# Sheet1.net
KiCad netlist of a schematic drawn in Altium Designer
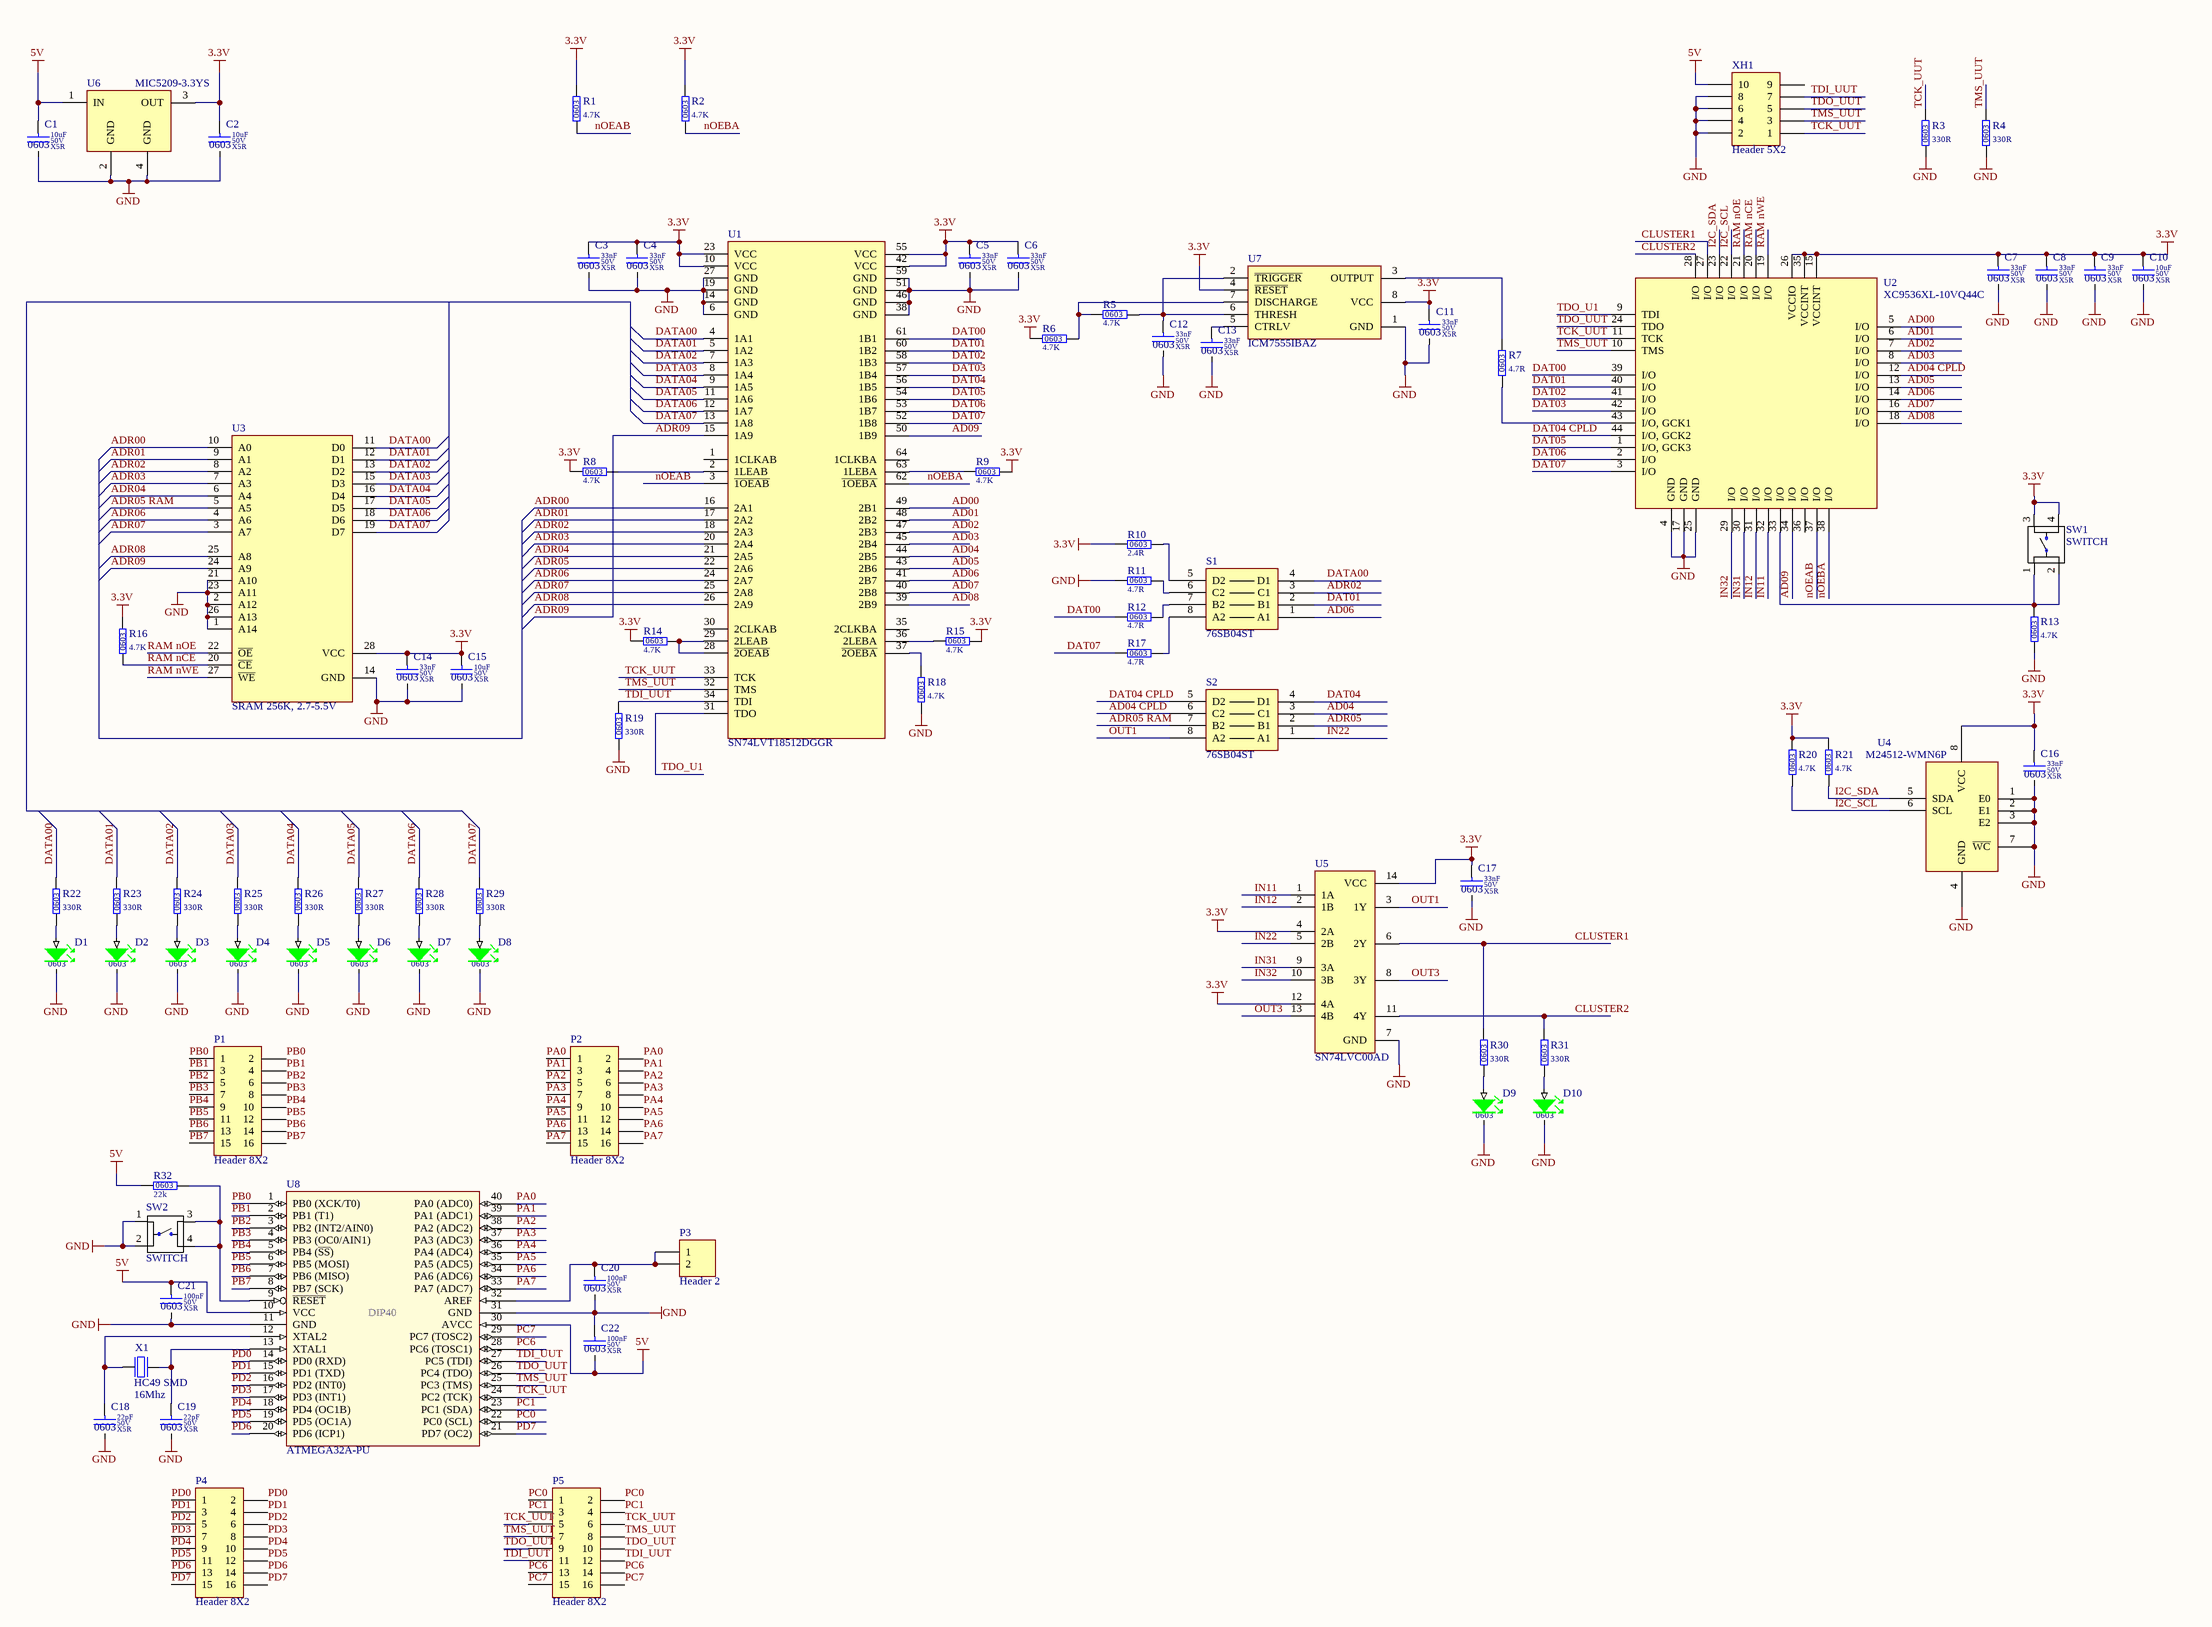
[diagram p0: Sheet1.SchDoc]

(export (version "E")
  (design (tool "Eeschema 10.0.6"))
  (components
    (comp (ref "C1")
      (value "10uF")
      (footprint "C_0603")
      (description "Capacitor")
      (fields
        (field (name "DIELECTRIC") "X5R")
        (field (name "VOLTAGE") "50V")
        (field (name "SCH_FOOTPRINT") "0603")
        (field (name "PART NUMBER") "C_10uF_50V_X5R_0603_10")
        (field (name "TOLERANCE") "10%")
      )
      (libsource (lib "MatyczLib") (part "C"))
    )
    (comp (ref "C2")
      (value "10uF")
      (footprint "C_0603")
      (description "Capacitor")
      (fields
        (field (name "DIELECTRIC") "X5R")
        (field (name "VOLTAGE") "50V")
        (field (name "SCH_FOOTPRINT") "0603")
        (field (name "PART NUMBER") "C_10uF_50V_X5R_0603_10")
        (field (name "TOLERANCE") "10%")
      )
      (libsource (lib "MatyczLib") (part "C"))
    )
    (comp (ref "C3")
      (value "33nF")
      (footprint "C_0603")
      (description "Capacitor")
      (fields
        (field (name "DIELECTRIC") "X5R")
        (field (name "VOLTAGE") "50V")
        (field (name "SCH_FOOTPRINT") "0603")
        (field (name "PART NUMBER") "C_33nF_50V_X5R_0603_10")
        (field (name "TOLERANCE") "10%")
      )
      (libsource (lib "MatyczLib") (part "C"))
    )
    (comp (ref "C4")
      (value "33nF")
      (footprint "C_0603")
      (description "Capacitor")
      (fields
        (field (name "DIELECTRIC") "X5R")
        (field (name "VOLTAGE") "50V")
        (field (name "SCH_FOOTPRINT") "0603")
        (field (name "PART NUMBER") "C_33nF_50V_X5R_0603_10")
        (field (name "TOLERANCE") "10%")
      )
      (libsource (lib "MatyczLib") (part "C"))
    )
    (comp (ref "C5")
      (value "33nF")
      (footprint "C_0603")
      (description "Capacitor")
      (fields
        (field (name "DIELECTRIC") "X5R")
        (field (name "VOLTAGE") "50V")
        (field (name "SCH_FOOTPRINT") "0603")
        (field (name "PART NUMBER") "C_33nF_50V_X5R_0603_10")
        (field (name "TOLERANCE") "10%")
      )
      (libsource (lib "MatyczLib") (part "C"))
    )
    (comp (ref "C6")
      (value "33nF")
      (footprint "C_0603")
      (description "Capacitor")
      (fields
        (field (name "DIELECTRIC") "X5R")
        (field (name "VOLTAGE") "50V")
        (field (name "SCH_FOOTPRINT") "0603")
        (field (name "PART NUMBER") "C_33nF_50V_X5R_0603_10")
        (field (name "TOLERANCE") "10%")
      )
      (libsource (lib "MatyczLib") (part "C"))
    )
    (comp (ref "C7")
      (value "33nF")
      (footprint "C_0603")
      (description "Capacitor")
      (fields
        (field (name "DIELECTRIC") "X5R")
        (field (name "VOLTAGE") "50V")
        (field (name "SCH_FOOTPRINT") "0603")
        (field (name "PART NUMBER") "C_33nF_50V_X5R_0603_10")
        (field (name "TOLERANCE") "10%")
      )
      (libsource (lib "MatyczLib") (part "C"))
    )
    (comp (ref "C8")
      (value "33nF")
      (footprint "C_0603")
      (description "Capacitor")
      (fields
        (field (name "DIELECTRIC") "X5R")
        (field (name "VOLTAGE") "50V")
        (field (name "SCH_FOOTPRINT") "0603")
        (field (name "PART NUMBER") "C_33nF_50V_X5R_0603_10")
        (field (name "TOLERANCE") "10%")
      )
      (libsource (lib "MatyczLib") (part "C"))
    )
    (comp (ref "C9")
      (value "33nF")
      (footprint "C_0603")
      (description "Capacitor")
      (fields
        (field (name "DIELECTRIC") "X5R")
        (field (name "VOLTAGE") "50V")
        (field (name "SCH_FOOTPRINT") "0603")
        (field (name "PART NUMBER") "C_33nF_50V_X5R_0603_10")
        (field (name "TOLERANCE") "10%")
      )
      (libsource (lib "MatyczLib") (part "C"))
    )
    (comp (ref "C10")
      (value "10uF")
      (footprint "C_0603")
      (description "Capacitor")
      (fields
        (field (name "DIELECTRIC") "X5R")
        (field (name "VOLTAGE") "50V")
        (field (name "SCH_FOOTPRINT") "0603")
        (field (name "PART NUMBER") "C_10uF_50V_X5R_0603_10")
        (field (name "TOLERANCE") "10%")
      )
      (libsource (lib "MatyczLib") (part "C"))
    )
    (comp (ref "C11")
      (value "33nF")
      (footprint "C_0603")
      (description "Capacitor")
      (fields
        (field (name "DIELECTRIC") "X5R")
        (field (name "VOLTAGE") "50V")
        (field (name "SCH_FOOTPRINT") "0603")
        (field (name "PART NUMBER") "C_33nF_50V_X5R_0603_10")
        (field (name "TOLERANCE") "10%")
      )
      (libsource (lib "MatyczLib") (part "C"))
    )
    (comp (ref "C12")
      (value "33nF")
      (footprint "C_0603")
      (description "Capacitor")
      (fields
        (field (name "DIELECTRIC") "X5R")
        (field (name "VOLTAGE") "50V")
        (field (name "SCH_FOOTPRINT") "0603")
        (field (name "PART NUMBER") "C_33nF_50V_X5R_0603_10")
        (field (name "TOLERANCE") "10%")
      )
      (libsource (lib "MatyczLib") (part "C"))
    )
    (comp (ref "C13")
      (value "33nF")
      (footprint "C_0603")
      (description "Capacitor")
      (fields
        (field (name "DIELECTRIC") "X5R")
        (field (name "VOLTAGE") "50V")
        (field (name "SCH_FOOTPRINT") "0603")
        (field (name "PART NUMBER") "C_33nF_50V_X5R_0603_10")
        (field (name "TOLERANCE") "10%")
      )
      (libsource (lib "MatyczLib") (part "C"))
    )
    (comp (ref "C14")
      (value "33nF")
      (footprint "C_0603")
      (description "Capacitor")
      (fields
        (field (name "DIELECTRIC") "X5R")
        (field (name "VOLTAGE") "50V")
        (field (name "SCH_FOOTPRINT") "0603")
        (field (name "PART NUMBER") "C_33nF_50V_X5R_0603_10")
        (field (name "TOLERANCE") "10%")
      )
      (libsource (lib "MatyczLib") (part "C"))
    )
    (comp (ref "C15")
      (value "10uF")
      (footprint "C_0603")
      (description "Capacitor")
      (fields
        (field (name "DIELECTRIC") "X5R")
        (field (name "VOLTAGE") "50V")
        (field (name "SCH_FOOTPRINT") "0603")
        (field (name "PART NUMBER") "C_10uF_50V_X5R_0603_10")
        (field (name "TOLERANCE") "10%")
      )
      (libsource (lib "MatyczLib") (part "C"))
    )
    (comp (ref "C16")
      (value "33nF")
      (footprint "C_0603")
      (description "Capacitor")
      (fields
        (field (name "DIELECTRIC") "X5R")
        (field (name "VOLTAGE") "50V")
        (field (name "SCH_FOOTPRINT") "0603")
        (field (name "PART NUMBER") "C_33nF_50V_X5R_0603_10")
        (field (name "TOLERANCE") "10%")
      )
      (libsource (lib "MatyczLib") (part "C"))
    )
    (comp (ref "C17")
      (value "33nF")
      (footprint "C_0603")
      (description "Capacitor")
      (fields
        (field (name "DIELECTRIC") "X5R")
        (field (name "VOLTAGE") "50V")
        (field (name "SCH_FOOTPRINT") "0603")
        (field (name "PART NUMBER") "C_33nF_50V_X5R_0603_10")
        (field (name "TOLERANCE") "10%")
      )
      (libsource (lib "MatyczLib") (part "C"))
    )
    (comp (ref "C18")
      (value "22pF")
      (footprint "C_0603")
      (description "Capacitor")
      (fields
        (field (name "DIELECTRIC") "X5R")
        (field (name "VOLTAGE") "50V")
        (field (name "SCH_FOOTPRINT") "0603")
        (field (name "PART NUMBER") "C_22pF_50V_X5R_0603_10")
        (field (name "TOLERANCE") "10%")
      )
      (libsource (lib "MatyczLib") (part "C"))
    )
    (comp (ref "C19")
      (value "22pF")
      (footprint "C_0603")
      (description "Capacitor")
      (fields
        (field (name "DIELECTRIC") "X5R")
        (field (name "VOLTAGE") "50V")
        (field (name "SCH_FOOTPRINT") "0603")
        (field (name "PART NUMBER") "C_22pF_50V_X5R_0603_10")
        (field (name "TOLERANCE") "10%")
      )
      (libsource (lib "MatyczLib") (part "C"))
    )
    (comp (ref "C20")
      (value "100nF")
      (footprint "C_0603")
      (description "Capacitor")
      (fields
        (field (name "DIELECTRIC") "X5R")
        (field (name "VOLTAGE") "50V")
        (field (name "SCH_FOOTPRINT") "0603")
        (field (name "PART NUMBER") "C_100nF_50V_X5R_0603_10")
        (field (name "TOLERANCE") "10%")
      )
      (libsource (lib "MatyczLib") (part "C"))
    )
    (comp (ref "C21")
      (value "100nF")
      (footprint "C_0603")
      (description "Capacitor")
      (fields
        (field (name "DIELECTRIC") "X5R")
        (field (name "VOLTAGE") "50V")
        (field (name "SCH_FOOTPRINT") "0603")
        (field (name "PART NUMBER") "C_100nF_50V_X5R_0603_10")
        (field (name "TOLERANCE") "10%")
      )
      (libsource (lib "MatyczLib") (part "C"))
    )
    (comp (ref "C22")
      (value "100nF")
      (footprint "C_0603")
      (description "Capacitor")
      (fields
        (field (name "DIELECTRIC") "X5R")
        (field (name "VOLTAGE") "50V")
        (field (name "SCH_FOOTPRINT") "0603")
        (field (name "PART NUMBER") "C_100nF_50V_X5R_0603_10")
        (field (name "TOLERANCE") "10%")
      )
      (libsource (lib "MatyczLib") (part "C"))
    )
    (comp (ref "D1")
      (value "Green Led")
      (footprint "OL_0603_1608")
      (description "LED GREEN")
      (fields
        (field (name "SCH_FOOTPRINT") "0603")
        (field (name "PART NUMBER") "OL_G_0603")
        (field (name "MANUFACTURER") "Lite-On")
      )
      (libsource (lib "Library") (part "OL_G"))
    )
    (comp (ref "D2")
      (value "Green Led")
      (footprint "OL_0603_1608")
      (description "LED GREEN")
      (fields
        (field (name "SCH_FOOTPRINT") "0603")
        (field (name "PART NUMBER") "OL_G_0603")
        (field (name "MANUFACTURER") "Lite-On")
      )
      (libsource (lib "Library") (part "OL_G"))
    )
    (comp (ref "D3")
      (value "Green Led")
      (footprint "OL_0603_1608")
      (description "LED GREEN")
      (fields
        (field (name "SCH_FOOTPRINT") "0603")
        (field (name "PART NUMBER") "OL_G_0603")
        (field (name "MANUFACTURER") "Lite-On")
      )
      (libsource (lib "Library") (part "OL_G"))
    )
    (comp (ref "D4")
      (value "Green Led")
      (footprint "OL_0603_1608")
      (description "LED GREEN")
      (fields
        (field (name "SCH_FOOTPRINT") "0603")
        (field (name "PART NUMBER") "OL_G_0603")
        (field (name "MANUFACTURER") "Lite-On")
      )
      (libsource (lib "Library") (part "OL_G"))
    )
    (comp (ref "D5")
      (value "Green Led")
      (footprint "OL_0603_1608")
      (description "LED GREEN")
      (fields
        (field (name "SCH_FOOTPRINT") "0603")
        (field (name "PART NUMBER") "OL_G_0603")
        (field (name "MANUFACTURER") "Lite-On")
      )
      (libsource (lib "Library") (part "OL_G"))
    )
    (comp (ref "D6")
      (value "Green Led")
      (footprint "OL_0603_1608")
      (description "LED GREEN")
      (fields
        (field (name "SCH_FOOTPRINT") "0603")
        (field (name "PART NUMBER") "OL_G_0603")
        (field (name "MANUFACTURER") "Lite-On")
      )
      (libsource (lib "Library") (part "OL_G"))
    )
    (comp (ref "D7")
      (value "Green Led")
      (footprint "OL_0603_1608")
      (description "LED GREEN")
      (fields
        (field (name "SCH_FOOTPRINT") "0603")
        (field (name "PART NUMBER") "OL_G_0603")
        (field (name "MANUFACTURER") "Lite-On")
      )
      (libsource (lib "Library") (part "OL_G"))
    )
    (comp (ref "D8")
      (value "Green Led")
      (footprint "OL_0603_1608")
      (description "LED GREEN")
      (fields
        (field (name "SCH_FOOTPRINT") "0603")
        (field (name "PART NUMBER") "OL_G_0603")
        (field (name "MANUFACTURER") "Lite-On")
      )
      (libsource (lib "Library") (part "OL_G"))
    )
    (comp (ref "D9")
      (value "Green Led")
      (footprint "OL_0603_1608")
      (description "LED GREEN")
      (fields
        (field (name "SCH_FOOTPRINT") "0603")
        (field (name "PART NUMBER") "OL_G_0603")
        (field (name "MANUFACTURER") "Lite-On")
      )
      (libsource (lib "Library") (part "OL_G"))
    )
    (comp (ref "D10")
      (value "Green Led")
      (footprint "OL_0603_1608")
      (description "LED GREEN")
      (fields
        (field (name "SCH_FOOTPRINT") "0603")
        (field (name "PART NUMBER") "OL_G_0603")
        (field (name "MANUFACTURER") "Lite-On")
      )
      (libsource (lib "Library") (part "OL_G"))
    )
    (comp (ref "P1")
      (value "Header 8X2")
      (footprint "HDR2X8")
      (description "Header, 8-Pin, Dual row")
      (fields (field (name "PUBLISHER") "Altium Limited"))
      (libsource (lib "Miscellaneous Connectors") (part "Header 8X2"))
    )
    (comp (ref "P2")
      (value "Header 8X2")
      (footprint "HDR2X8")
      (description "Header, 8-Pin, Dual row")
      (fields (field (name "PUBLISHER") "Altium Limited"))
      (libsource (lib "Miscellaneous Connectors") (part "Header 8X2"))
    )
    (comp (ref "P3")
      (value "Header 2")
      (footprint "HDR1X2")
      (description "Header, 2-Pin")
      (fields (field (name "PUBLISHER") "Altium Limited"))
      (libsource (lib "Miscellaneous Connectors") (part "Header 2"))
    )
    (comp (ref "P4")
      (value "Header 8X2")
      (footprint "HDR2X8")
      (description "Header, 8-Pin, Dual row")
      (fields (field (name "PUBLISHER") "Altium Limited"))
      (libsource (lib "Miscellaneous Connectors") (part "Header 8X2"))
    )
    (comp (ref "P5")
      (value "Header 8X2")
      (footprint "HDR2X8")
      (description "Header, 8-Pin, Dual row")
      (fields (field (name "PUBLISHER") "Altium Limited"))
      (libsource (lib "Miscellaneous Connectors") (part "Header 8X2"))
    )
    (comp (ref "R1")
      (value "4.7K")
      (footprint "R_0603")
      (fields
        (field (name "SCH_FOOTPRINT") "0603")
        (field (name "PART NUMBER") "R_4.7k_0603_5")
        (field (name "TOLERANCE") "5%")
        (field (name "POWER") "100mW")
      )
      (libsource (lib "") (part "R_1"))
    )
    (comp (ref "R2")
      (value "4.7K")
      (footprint "R_0603")
      (fields
        (field (name "SCH_FOOTPRINT") "0603")
        (field (name "PART NUMBER") "R_4.7k_0603_5")
        (field (name "TOLERANCE") "5%")
        (field (name "POWER") "100mW")
      )
      (libsource (lib "") (part "R_1"))
    )
    (comp (ref "R3")
      (value "330R")
      (footprint "R_0603")
      (fields
        (field (name "SCH_FOOTPRINT") "0603")
        (field (name "PART NUMBER") "R_330R_0603_5")
        (field (name "TOLERANCE") "5%")
        (field (name "POWER") "100mW")
      )
      (libsource (lib "") (part "R_1"))
    )
    (comp (ref "R4")
      (value "330R")
      (footprint "R_0603")
      (fields
        (field (name "SCH_FOOTPRINT") "0603")
        (field (name "PART NUMBER") "R_330R_0603_5")
        (field (name "TOLERANCE") "5%")
        (field (name "POWER") "100mW")
      )
      (libsource (lib "") (part "R_1"))
    )
    (comp (ref "R5")
      (value "4.7K")
      (footprint "R_0603")
      (fields
        (field (name "SCH_FOOTPRINT") "0603")
        (field (name "PART NUMBER") "R_4.7k_0603_5")
        (field (name "TOLERANCE") "5%")
        (field (name "POWER") "100mW")
      )
      (libsource (lib "MatyczLib") (part "R"))
    )
    (comp (ref "R6")
      (value "4.7K")
      (footprint "R_0603")
      (fields
        (field (name "SCH_FOOTPRINT") "0603")
        (field (name "PART NUMBER") "R_4.7k_0603_5")
        (field (name "TOLERANCE") "5%")
        (field (name "POWER") "100mW")
      )
      (libsource (lib "MatyczLib") (part "R"))
    )
    (comp (ref "R7")
      (value "4.7R")
      (footprint "R_0603")
      (fields
        (field (name "SCH_FOOTPRINT") "0603")
        (field (name "PART NUMBER") "R_4.7R_0603_5")
        (field (name "TOLERANCE") "5%")
        (field (name "POWER") "100mW")
      )
      (libsource (lib "") (part "R_1"))
    )
    (comp (ref "R8")
      (value "4.7K")
      (footprint "R_0603")
      (fields
        (field (name "SCH_FOOTPRINT") "0603")
        (field (name "PART NUMBER") "R_4.7k_0603_5")
        (field (name "TOLERANCE") "5%")
        (field (name "POWER") "100mW")
      )
      (libsource (lib "MatyczLib") (part "R"))
    )
    (comp (ref "R9")
      (value "4.7K")
      (footprint "R_0603")
      (fields
        (field (name "SCH_FOOTPRINT") "0603")
        (field (name "PART NUMBER") "R_4.7k_0603_5")
        (field (name "TOLERANCE") "5%")
        (field (name "POWER") "100mW")
      )
      (libsource (lib "MatyczLib") (part "R"))
    )
    (comp (ref "R10")
      (value "2.4R")
      (footprint "R_0603")
      (fields
        (field (name "SCH_FOOTPRINT") "0603")
        (field (name "PART NUMBER") "R_2.4R_0603_5")
        (field (name "TOLERANCE") "5%")
        (field (name "POWER") "100mW")
      )
      (libsource (lib "MatyczLib") (part "R"))
    )
    (comp (ref "R11")
      (value "4.7R")
      (footprint "R_0603")
      (fields
        (field (name "SCH_FOOTPRINT") "0603")
        (field (name "PART NUMBER") "R_4.7R_0603_5")
        (field (name "TOLERANCE") "5%")
        (field (name "POWER") "100mW")
      )
      (libsource (lib "MatyczLib") (part "R"))
    )
    (comp (ref "R12")
      (value "4.7R")
      (footprint "R_0603")
      (fields
        (field (name "SCH_FOOTPRINT") "0603")
        (field (name "PART NUMBER") "R_4.7R_0603_5")
        (field (name "TOLERANCE") "5%")
        (field (name "POWER") "100mW")
      )
      (libsource (lib "MatyczLib") (part "R"))
    )
    (comp (ref "R13")
      (value "4.7K")
      (footprint "R_0603")
      (fields
        (field (name "SCH_FOOTPRINT") "0603")
        (field (name "PART NUMBER") "R_4.7k_0603_5")
        (field (name "TOLERANCE") "5%")
        (field (name "POWER") "100mW")
      )
      (libsource (lib "") (part "R_1"))
    )
    (comp (ref "R14")
      (value "4.7K")
      (footprint "R_0603")
      (fields
        (field (name "SCH_FOOTPRINT") "0603")
        (field (name "PART NUMBER") "R_4.7k_0603_5")
        (field (name "TOLERANCE") "5%")
        (field (name "POWER") "100mW")
      )
      (libsource (lib "MatyczLib") (part "R"))
    )
    (comp (ref "R15")
      (value "4.7K")
      (footprint "R_0603")
      (fields
        (field (name "SCH_FOOTPRINT") "0603")
        (field (name "PART NUMBER") "R_4.7k_0603_5")
        (field (name "TOLERANCE") "5%")
        (field (name "POWER") "100mW")
      )
      (libsource (lib "MatyczLib") (part "R"))
    )
    (comp (ref "R16")
      (value "4.7K")
      (footprint "R_0603")
      (fields
        (field (name "SCH_FOOTPRINT") "0603")
        (field (name "PART NUMBER") "R_4.7k_0603_5")
        (field (name "TOLERANCE") "5%")
        (field (name "POWER") "100mW")
      )
      (libsource (lib "") (part "R_1"))
    )
    (comp (ref "R17")
      (value "4.7R")
      (footprint "R_0603")
      (fields
        (field (name "SCH_FOOTPRINT") "0603")
        (field (name "PART NUMBER") "R_4.7R_0603_5")
        (field (name "TOLERANCE") "5%")
        (field (name "POWER") "100mW")
      )
      (libsource (lib "MatyczLib") (part "R"))
    )
    (comp (ref "R18")
      (value "4.7K")
      (footprint "R_0603")
      (fields
        (field (name "SCH_FOOTPRINT") "0603")
        (field (name "PART NUMBER") "R_4.7k_0603_5")
        (field (name "TOLERANCE") "5%")
        (field (name "POWER") "100mW")
      )
      (libsource (lib "") (part "R_1"))
    )
    (comp (ref "R19")
      (value "330R")
      (footprint "R_0603")
      (fields
        (field (name "SCH_FOOTPRINT") "0603")
        (field (name "PART NUMBER") "R_330R_0603_5")
        (field (name "TOLERANCE") "5%")
        (field (name "POWER") "100mW")
      )
      (libsource (lib "") (part "R_1"))
    )
    (comp (ref "R20")
      (value "4.7K")
      (footprint "R_0603")
      (fields
        (field (name "SCH_FOOTPRINT") "0603")
        (field (name "PART NUMBER") "R_4.7k_0603_5")
        (field (name "TOLERANCE") "5%")
        (field (name "POWER") "100mW")
      )
      (libsource (lib "") (part "R_1"))
    )
    (comp (ref "R21")
      (value "4.7K")
      (footprint "R_0603")
      (fields
        (field (name "SCH_FOOTPRINT") "0603")
        (field (name "PART NUMBER") "R_4.7k_0603_5")
        (field (name "TOLERANCE") "5%")
        (field (name "POWER") "100mW")
      )
      (libsource (lib "") (part "R_1"))
    )
    (comp (ref "R22")
      (value "330R")
      (footprint "R_0603")
      (fields
        (field (name "SCH_FOOTPRINT") "0603")
        (field (name "PART NUMBER") "R_330R_0603_5")
        (field (name "TOLERANCE") "5%")
        (field (name "POWER") "100mW")
      )
      (libsource (lib "") (part "R_1"))
    )
    (comp (ref "R23")
      (value "330R")
      (footprint "R_0603")
      (fields
        (field (name "SCH_FOOTPRINT") "0603")
        (field (name "PART NUMBER") "R_330R_0603_5")
        (field (name "TOLERANCE") "5%")
        (field (name "POWER") "100mW")
      )
      (libsource (lib "") (part "R_1"))
    )
    (comp (ref "R24")
      (value "330R")
      (footprint "R_0603")
      (fields
        (field (name "SCH_FOOTPRINT") "0603")
        (field (name "PART NUMBER") "R_330R_0603_5")
        (field (name "TOLERANCE") "5%")
        (field (name "POWER") "100mW")
      )
      (libsource (lib "") (part "R_1"))
    )
    (comp (ref "R25")
      (value "330R")
      (footprint "R_0603")
      (fields
        (field (name "SCH_FOOTPRINT") "0603")
        (field (name "PART NUMBER") "R_330R_0603_5")
        (field (name "TOLERANCE") "5%")
        (field (name "POWER") "100mW")
      )
      (libsource (lib "") (part "R_1"))
    )
    (comp (ref "R26")
      (value "330R")
      (footprint "R_0603")
      (fields
        (field (name "SCH_FOOTPRINT") "0603")
        (field (name "PART NUMBER") "R_330R_0603_5")
        (field (name "TOLERANCE") "5%")
        (field (name "POWER") "100mW")
      )
      (libsource (lib "") (part "R_1"))
    )
    (comp (ref "R27")
      (value "330R")
      (footprint "R_0603")
      (fields
        (field (name "SCH_FOOTPRINT") "0603")
        (field (name "PART NUMBER") "R_330R_0603_5")
        (field (name "TOLERANCE") "5%")
        (field (name "POWER") "100mW")
      )
      (libsource (lib "") (part "R_1"))
    )
    (comp (ref "R28")
      (value "330R")
      (footprint "R_0603")
      (fields
        (field (name "SCH_FOOTPRINT") "0603")
        (field (name "PART NUMBER") "R_330R_0603_5")
        (field (name "TOLERANCE") "5%")
        (field (name "POWER") "100mW")
      )
      (libsource (lib "") (part "R_1"))
    )
    (comp (ref "R29")
      (value "330R")
      (footprint "R_0603")
      (fields
        (field (name "SCH_FOOTPRINT") "0603")
        (field (name "PART NUMBER") "R_330R_0603_5")
        (field (name "TOLERANCE") "5%")
        (field (name "POWER") "100mW")
      )
      (libsource (lib "") (part "R_1"))
    )
    (comp (ref "R30")
      (value "330R")
      (footprint "R_0603")
      (fields
        (field (name "SCH_FOOTPRINT") "0603")
        (field (name "PART NUMBER") "R_330R_0603_5")
        (field (name "TOLERANCE") "5%")
        (field (name "POWER") "100mW")
      )
      (libsource (lib "") (part "R_1"))
    )
    (comp (ref "R31")
      (value "330R")
      (footprint "R_0603")
      (fields
        (field (name "SCH_FOOTPRINT") "0603")
        (field (name "PART NUMBER") "R_330R_0603_5")
        (field (name "TOLERANCE") "5%")
        (field (name "POWER") "100mW")
      )
      (libsource (lib "") (part "R_1"))
    )
    (comp (ref "R32")
      (value "22k")
      (footprint "R_0603")
      (fields
        (field (name "SCH_FOOTPRINT") "0603")
        (field (name "PART NUMBER") "R_22k_0603_5")
        (field (name "TOLERANCE") "5%")
        (field (name "POWER") "100mW")
      )
      (libsource (lib "MatyczLib") (part "R"))
    )
    (comp (ref "S1") (value "76SB04ST") (footprint "DIP8_sw") (libsource (lib "Schlib1") (part "76SB04ST")))
    (comp (ref "S2") (value "76SB04ST") (footprint "DIP8_sw") (libsource (lib "Schlib1") (part "76SB04ST")))
    (comp (ref "SW1") (value "SWITCH") (footprint "switch") (libsource (lib "Schlib1") (part "SWITCH")))
    (comp (ref "SW2") (value "SWITCH") (footprint "switch") (libsource (lib "Schlib1") (part "SWITCH")))
    (comp (ref "U1")
      (value "SN74LVT18512DGGR")
      (footprint "TSSOP50P810X105-64N")
      (description "IC SCAN TEST UNIV TXRX 64TSSOP")
      (libsource (lib "Schlib1") (part "SN74LVT18512DGGR"))
    )
    (comp (ref "U2")
      (value "XC9536XL-10VQ44C")
      (footprint "TQFP80P1200X1200X120-44N")
      (description "IC CPLD 36MC 10NS 44VQFP")
      (libsource (lib "Schlib1") (part "XC9536XL-10VQ44C"))
    )
    (comp (ref "U3")
      (value "SRAM 256K, 2.7-5.5V")
      (footprint "DIP28")
      (description "SRAM 256K, 2.7-5.5V, 70ns 32K x 8 Asynch SRAM")
      (libsource (lib "Schlib1") (part "AS6C62256A-70PCN"))
    )
    (comp (ref "U4")
      (value "M24512-WMN6P")
      (footprint "SOIC127P600X171-8N")
      (description "IC EEPROM 512K I2C 1MHZ 8SO")
      (libsource (lib "Schlib1") (part "M24512-WMN6P"))
    )
    (comp (ref "U5")
      (value "SN74LVC00AD")
      (footprint "SOIC127P600X175-14N")
      (description "IC GATE NAND 4CH 2-INP 14SOIC")
      (libsource (lib "Schlib1") (part "SN74LVC00AD"))
    )
    (comp (ref "U6")
      (value "MIC5209-3.3YS")
      (footprint "SOT230P700X180-4N")
      (description "IC REG LINEAR 3.3V 500MA SOT223")
      (libsource (lib "Schlib1") (part "MIC5209-3.3YS"))
    )
    (comp (ref "U7")
      (value "ICM7555IBAZ")
      (footprint "SOIC127P600X171-8N")
      (description "INTERSIL         ICM7555IBAZ             IC, TIMER CMOS, SMD, 7555, SOIC8")
      (libsource (lib "Schlib1") (part "ICM7555IBAZ"))
    )
    (comp (ref "U8")
      (value "ATMEGA32A-PU")
      (footprint "DIP40_SOCKET")
      (fields
        (field (name "SCH_FOOTPRINT") "DIP40")
        (field (name "PART NUMBER") "UP_ATMEGA32A-PU")
        (field (name "MANUFACTURER") "Microchip")
      )
      (libsource (lib "MatyczLib") (part "UP_ATMEGA32A-PU"))
    )
    (comp (ref "X1")
      (value "16Mhz")
      (footprint "X_HC49_SMD")
      (description "Resonator Ceramic")
      (fields
        (field (name "SCH_FOOTPRINT") "HC49 SMD")
        (field (name "PART NUMBER") "X_HC49_SMD")
        (field (name "Comment") "16Mhz crystal")
      )
      (libsource (lib "MatyczLib") (part "X_GENERIC"))
    )
    (comp (ref "XH1")
      (value "Header 5X2")
      (footprint "HDR2X5")
      (description "Header, 5-Pin, Dual row")
      (fields (field (name "PUBLISHER") "Altium Limited"))
      (libsource (lib "Miscellaneous Connectors") (part "Header 5X2"))
    )
  )
  (nets
    (net (code "1") (name "/AD00") (class "Default")
      (node (ref "U1") (pin "49") (pinfunction "2B1_49") (pintype "passive"))
      (node (ref "U2") (pin "5") (pinfunction "I/O_5") (pintype "passive"))
    )
    (net (code "2") (name "/AD01") (class "Default")
      (node (ref "U1") (pin "48") (pinfunction "2B2_48") (pintype "passive"))
      (node (ref "U2") (pin "6") (pinfunction "I/O_6") (pintype "passive"))
    )
    (net (code "3") (name "/AD02") (class "Default")
      (node (ref "U1") (pin "47") (pinfunction "2B3_47") (pintype "passive"))
      (node (ref "U2") (pin "7") (pinfunction "I/O_7") (pintype "passive"))
    )
    (net (code "4") (name "/AD03") (class "Default")
      (node (ref "U1") (pin "45") (pinfunction "2B4_45") (pintype "passive"))
      (node (ref "U2") (pin "8") (pinfunction "I/O_8") (pintype "passive"))
    )
    (net (code "5") (name "/AD04") (class "Default")
      (node (ref "S2") (pin "3") (pinfunction "C1_3") (pintype "passive"))
      (node (ref "U1") (pin "44") (pinfunction "2B5_44") (pintype "passive"))
    )
    (net (code "6") (name "/AD04 CPLD") (class "Default")
      (node (ref "S2") (pin "6") (pinfunction "C2_6") (pintype "passive"))
      (node (ref "U2") (pin "12") (pinfunction "I/O_12") (pintype "passive"))
    )
    (net (code "7") (name "/AD05") (class "Default")
      (node (ref "U1") (pin "43") (pinfunction "2B6_43") (pintype "passive"))
      (node (ref "U2") (pin "13") (pinfunction "I/O_13") (pintype "passive"))
    )
    (net (code "8") (name "/AD06") (class "Default")
      (node (ref "S1") (pin "1") (pinfunction "A1_1") (pintype "passive"))
      (node (ref "U1") (pin "41") (pinfunction "2B7_41") (pintype "passive"))
      (node (ref "U2") (pin "14") (pinfunction "I/O_14") (pintype "passive"))
    )
    (net (code "9") (name "/AD07") (class "Default")
      (node (ref "U1") (pin "40") (pinfunction "2B8_40") (pintype "passive"))
      (node (ref "U2") (pin "16") (pinfunction "I/O_16") (pintype "passive"))
    )
    (net (code "10") (name "/AD08") (class "Default")
      (node (ref "U1") (pin "39") (pinfunction "2B9_39") (pintype "passive"))
      (node (ref "U2") (pin "18") (pinfunction "I/O_18") (pintype "passive"))
    )
    (net (code "11") (name "/AD09") (class "Default")
      (node (ref "U1") (pin "50") (pinfunction "1B9_50") (pintype "passive"))
      (node (ref "U2") (pin "34") (pinfunction "I/O_34") (pintype "passive"))
    )
    (net (code "12") (name "/ADR00") (class "Default")
      (node (ref "U1") (pin "16") (pinfunction "2A1_16") (pintype "passive"))
      (node (ref "U3") (pin "10") (pinfunction "A0_10") (pintype "passive"))
    )
    (net (code "13") (name "/ADR01") (class "Default")
      (node (ref "U1") (pin "17") (pinfunction "2A2_17") (pintype "passive"))
      (node (ref "U3") (pin "9") (pinfunction "A1_9") (pintype "passive"))
    )
    (net (code "14") (name "/ADR02") (class "Default")
      (node (ref "S1") (pin "3") (pinfunction "C1_3") (pintype "passive"))
      (node (ref "U1") (pin "18") (pinfunction "2A3_18") (pintype "passive"))
      (node (ref "U3") (pin "8") (pinfunction "A2_8") (pintype "passive"))
    )
    (net (code "15") (name "/ADR03") (class "Default")
      (node (ref "U1") (pin "20") (pinfunction "2A4_20") (pintype "passive"))
      (node (ref "U3") (pin "7") (pinfunction "A3_7") (pintype "passive"))
    )
    (net (code "16") (name "/ADR04") (class "Default")
      (node (ref "U1") (pin "21") (pinfunction "2A5_21") (pintype "passive"))
      (node (ref "U3") (pin "6") (pinfunction "A4_6") (pintype "passive"))
    )
    (net (code "17") (name "/ADR05") (class "Default")
      (node (ref "S2") (pin "2") (pinfunction "B1_2") (pintype "passive"))
      (node (ref "U1") (pin "22") (pinfunction "2A6_22") (pintype "passive"))
    )
    (net (code "18") (name "/ADR05 RAM") (class "Default")
      (node (ref "S2") (pin "7") (pinfunction "B2_7") (pintype "passive"))
      (node (ref "U3") (pin "5") (pinfunction "A5_5") (pintype "passive"))
    )
    (net (code "19") (name "/ADR06") (class "Default")
      (node (ref "U1") (pin "24") (pinfunction "2A7_24") (pintype "passive"))
      (node (ref "U3") (pin "4") (pinfunction "A6_4") (pintype "passive"))
    )
    (net (code "20") (name "/ADR07") (class "Default")
      (node (ref "U1") (pin "25") (pinfunction "2A8_25") (pintype "passive"))
      (node (ref "U3") (pin "3") (pinfunction "A7_3") (pintype "passive"))
    )
    (net (code "21") (name "/ADR08") (class "Default")
      (node (ref "U1") (pin "26") (pinfunction "2A9_26") (pintype "passive"))
      (node (ref "U3") (pin "25") (pinfunction "A8_25") (pintype "passive"))
    )
    (net (code "22") (name "/ADR09") (class "Default")
      (node (ref "U1") (pin "15") (pinfunction "1A9_15") (pintype "passive"))
      (node (ref "U3") (pin "24") (pinfunction "A9_24") (pintype "passive"))
    )
    (net (code "23") (name "/CLUSTER1") (class "Default")
      (node (ref "R30") (pin "2") (pinfunction "2_2") (pintype "passive"))
      (node (ref "U2") (pin "27") (pinfunction "I/O_27") (pintype "passive"))
      (node (ref "U5") (pin "6") (pinfunction "2Y_6") (pintype "passive"))
    )
    (net (code "24") (name "/CLUSTER2") (class "Default")
      (node (ref "R31") (pin "2") (pinfunction "2_2") (pintype "passive"))
      (node (ref "U2") (pin "28") (pinfunction "I/O_28") (pintype "passive"))
      (node (ref "U5") (pin "11") (pinfunction "4Y_11") (pintype "passive"))
    )
    (net (code "25") (name "/DAT00") (class "Default")
      (node (ref "R12") (pin "1") (pinfunction "1_1") (pintype "passive"))
      (node (ref "U1") (pin "61") (pinfunction "1B1_61") (pintype "passive"))
      (node (ref "U2") (pin "39") (pinfunction "I/O_39") (pintype "passive"))
    )
    (net (code "26") (name "/DAT01") (class "Default")
      (node (ref "S1") (pin "2") (pinfunction "B1_2") (pintype "passive"))
      (node (ref "U1") (pin "60") (pinfunction "1B2_60") (pintype "passive"))
      (node (ref "U2") (pin "40") (pinfunction "I/O_40") (pintype "passive"))
    )
    (net (code "27") (name "/DAT02") (class "Default")
      (node (ref "U1") (pin "58") (pinfunction "1B3_58") (pintype "passive"))
      (node (ref "U2") (pin "41") (pinfunction "I/O_41") (pintype "passive"))
    )
    (net (code "28") (name "/DAT03") (class "Default")
      (node (ref "U1") (pin "57") (pinfunction "1B4_57") (pintype "passive"))
      (node (ref "U2") (pin "42") (pinfunction "I/O_42") (pintype "passive"))
    )
    (net (code "29") (name "/DAT04") (class "Default")
      (node (ref "S2") (pin "4") (pinfunction "D1_4") (pintype "passive"))
      (node (ref "U1") (pin "56") (pinfunction "1B5_56") (pintype "passive"))
    )
    (net (code "30") (name "/DAT04 CPLD") (class "Default")
      (node (ref "S2") (pin "5") (pinfunction "D2_5") (pintype "passive"))
      (node (ref "U2") (pin "44") (pinfunction "I/O,_GCK2_44") (pintype "passive"))
    )
    (net (code "31") (name "/DAT05") (class "Default")
      (node (ref "U1") (pin "54") (pinfunction "1B6_54") (pintype "passive"))
      (node (ref "U2") (pin "1") (pinfunction "I/O,_GCK3_1") (pintype "passive"))
    )
    (net (code "32") (name "/DAT06") (class "Default")
      (node (ref "U1") (pin "53") (pinfunction "1B7_53") (pintype "passive"))
      (node (ref "U2") (pin "2") (pinfunction "I/O_2") (pintype "passive"))
    )
    (net (code "33") (name "/DAT07") (class "Default")
      (node (ref "R17") (pin "1") (pinfunction "1_1") (pintype "passive"))
      (node (ref "U1") (pin "52") (pinfunction "1B8_52") (pintype "passive"))
      (node (ref "U2") (pin "3") (pinfunction "I/O_3") (pintype "passive"))
    )
    (net (code "34") (name "/DATA00") (class "Default")
      (node (ref "R22") (pin "2") (pinfunction "2_2") (pintype "passive"))
      (node (ref "S1") (pin "4") (pinfunction "D1_4") (pintype "passive"))
      (node (ref "U1") (pin "4") (pinfunction "1A1_4") (pintype "passive"))
      (node (ref "U3") (pin "11") (pinfunction "D0_11") (pintype "passive"))
    )
    (net (code "35") (name "/DATA01") (class "Default")
      (node (ref "R23") (pin "2") (pinfunction "2_2") (pintype "passive"))
      (node (ref "U1") (pin "5") (pinfunction "1A2_5") (pintype "passive"))
      (node (ref "U3") (pin "12") (pinfunction "D1_12") (pintype "passive"))
    )
    (net (code "36") (name "/DATA02") (class "Default")
      (node (ref "R24") (pin "2") (pinfunction "2_2") (pintype "passive"))
      (node (ref "U1") (pin "7") (pinfunction "1A3_7") (pintype "passive"))
      (node (ref "U3") (pin "13") (pinfunction "D2_13") (pintype "passive"))
    )
    (net (code "37") (name "/DATA03") (class "Default")
      (node (ref "R25") (pin "2") (pinfunction "2_2") (pintype "passive"))
      (node (ref "U1") (pin "8") (pinfunction "1A4_8") (pintype "passive"))
      (node (ref "U3") (pin "15") (pinfunction "D3_15") (pintype "passive"))
    )
    (net (code "38") (name "/DATA04") (class "Default")
      (node (ref "R26") (pin "2") (pinfunction "2_2") (pintype "passive"))
      (node (ref "U1") (pin "9") (pinfunction "1A5_9") (pintype "passive"))
      (node (ref "U3") (pin "16") (pinfunction "D4_16") (pintype "passive"))
    )
    (net (code "39") (name "/DATA05") (class "Default")
      (node (ref "R27") (pin "2") (pinfunction "2_2") (pintype "passive"))
      (node (ref "U1") (pin "11") (pinfunction "1A6_11") (pintype "passive"))
      (node (ref "U3") (pin "17") (pinfunction "D5_17") (pintype "passive"))
    )
    (net (code "40") (name "/DATA06") (class "Default")
      (node (ref "R28") (pin "2") (pinfunction "2_2") (pintype "passive"))
      (node (ref "U1") (pin "12") (pinfunction "1A7_12") (pintype "passive"))
      (node (ref "U3") (pin "18") (pinfunction "D6_18") (pintype "passive"))
    )
    (net (code "41") (name "/DATA07") (class "Default")
      (node (ref "R29") (pin "2") (pinfunction "2_2") (pintype "passive"))
      (node (ref "U1") (pin "13") (pinfunction "1A8_13") (pintype "passive"))
      (node (ref "U3") (pin "19") (pinfunction "D7_19") (pintype "passive"))
    )
    (net (code "42") (name "/I2C_SCL") (class "Default")
      (node (ref "R20") (pin "1") (pinfunction "1_1") (pintype "passive"))
      (node (ref "U2") (pin "22") (pinfunction "I/O_22") (pintype "passive"))
      (node (ref "U4") (pin "6") (pinfunction "SCL_6") (pintype "passive"))
    )
    (net (code "43") (name "/I2C_SDA") (class "Default")
      (node (ref "R21") (pin "1") (pinfunction "1_1") (pintype "passive"))
      (node (ref "U2") (pin "23") (pinfunction "I/O_23") (pintype "passive"))
      (node (ref "U4") (pin "5") (pinfunction "SDA_5") (pintype "passive"))
    )
    (net (code "44") (name "/IN11") (class "Default")
      (node (ref "U2") (pin "32") (pinfunction "I/O_32") (pintype "passive"))
      (node (ref "U5") (pin "1") (pinfunction "1A_1") (pintype "passive"))
    )
    (net (code "45") (name "/IN12") (class "Default")
      (node (ref "U2") (pin "31") (pinfunction "I/O_31") (pintype "passive"))
      (node (ref "U5") (pin "2") (pinfunction "1B_2") (pintype "passive"))
    )
    (net (code "46") (name "/IN22") (class "Default")
      (node (ref "S2") (pin "1") (pinfunction "A1_1") (pintype "passive"))
      (node (ref "U5") (pin "5") (pinfunction "2B_5") (pintype "passive"))
    )
    (net (code "47") (name "/IN31") (class "Default")
      (node (ref "U2") (pin "30") (pinfunction "I/O_30") (pintype "passive"))
      (node (ref "U5") (pin "9") (pinfunction "3A_9") (pintype "passive"))
    )
    (net (code "48") (name "/IN32") (class "Default")
      (node (ref "U2") (pin "29") (pinfunction "I/O_29") (pintype "passive"))
      (node (ref "U5") (pin "10") (pinfunction "3B_10") (pintype "passive"))
    )
    (net (code "49") (name "/OUT1") (class "Default")
      (node (ref "S2") (pin "8") (pinfunction "A2_8") (pintype "passive"))
      (node (ref "U5") (pin "3") (pinfunction "1Y_3") (pintype "passive"))
    )
    (net (code "50") (name "/OUT3") (class "Default")
      (node (ref "U5") (pin "13") (pinfunction "4B_13") (pintype "passive"))
      (node (ref "U5") (pin "8") (pinfunction "3Y_8") (pintype "passive"))
    )
    (net (code "51") (name "/PA0") (class "Default")
      (node (ref "P2") (pin "1") (pinfunction "1_1") (pintype "passive"))
      (node (ref "P2") (pin "2") (pinfunction "2_2") (pintype "passive"))
      (node (ref "U8") (pin "40") (pinfunction "PA0_(ADC0)_40") (pintype "bidirectional"))
    )
    (net (code "52") (name "/PA1") (class "Default")
      (node (ref "P2") (pin "3") (pinfunction "3_3") (pintype "passive"))
      (node (ref "P2") (pin "4") (pinfunction "4_4") (pintype "passive"))
      (node (ref "U8") (pin "39") (pinfunction "PA1_(ADC1)_39") (pintype "bidirectional"))
    )
    (net (code "53") (name "/PA2") (class "Default")
      (node (ref "P2") (pin "5") (pinfunction "5_5") (pintype "passive"))
      (node (ref "P2") (pin "6") (pinfunction "6_6") (pintype "passive"))
      (node (ref "U8") (pin "38") (pinfunction "PA2_(ADC2)_38") (pintype "bidirectional"))
    )
    (net (code "54") (name "/PA3") (class "Default")
      (node (ref "P2") (pin "7") (pinfunction "7_7") (pintype "passive"))
      (node (ref "P2") (pin "8") (pinfunction "8_8") (pintype "passive"))
      (node (ref "U8") (pin "37") (pinfunction "PA3_(ADC3)_37") (pintype "bidirectional"))
    )
    (net (code "55") (name "/PA4") (class "Default")
      (node (ref "P2") (pin "10") (pinfunction "10_10") (pintype "passive"))
      (node (ref "P2") (pin "9") (pinfunction "9_9") (pintype "passive"))
      (node (ref "U8") (pin "36") (pinfunction "PA4_(ADC4)_36") (pintype "bidirectional"))
    )
    (net (code "56") (name "/PA5") (class "Default")
      (node (ref "P2") (pin "11") (pinfunction "11_11") (pintype "passive"))
      (node (ref "P2") (pin "12") (pinfunction "12_12") (pintype "passive"))
      (node (ref "U8") (pin "35") (pinfunction "PA5_(ADC5)_35") (pintype "bidirectional"))
    )
    (net (code "57") (name "/PA6") (class "Default")
      (node (ref "P2") (pin "13") (pinfunction "13_13") (pintype "passive"))
      (node (ref "P2") (pin "14") (pinfunction "14_14") (pintype "passive"))
      (node (ref "U8") (pin "34") (pinfunction "PA6_(ADC6)_34") (pintype "bidirectional"))
    )
    (net (code "58") (name "/PA7") (class "Default")
      (node (ref "P2") (pin "15") (pinfunction "15_15") (pintype "passive"))
      (node (ref "P2") (pin "16") (pinfunction "16_16") (pintype "passive"))
      (node (ref "U8") (pin "33") (pinfunction "PA7_(ADC7)_33") (pintype "bidirectional"))
    )
    (net (code "59") (name "/PB0") (class "Default")
      (node (ref "P1") (pin "1") (pinfunction "1_1") (pintype "passive"))
      (node (ref "P1") (pin "2") (pinfunction "2_2") (pintype "passive"))
      (node (ref "U8") (pin "1") (pinfunction "PB0_(XCK/T0)_1") (pintype "bidirectional"))
    )
    (net (code "60") (name "/PB1") (class "Default")
      (node (ref "P1") (pin "3") (pinfunction "3_3") (pintype "passive"))
      (node (ref "P1") (pin "4") (pinfunction "4_4") (pintype "passive"))
      (node (ref "U8") (pin "2") (pinfunction "PB1_(T1)_2") (pintype "bidirectional"))
    )
    (net (code "61") (name "/PB2") (class "Default")
      (node (ref "P1") (pin "5") (pinfunction "5_5") (pintype "passive"))
      (node (ref "P1") (pin "6") (pinfunction "6_6") (pintype "passive"))
      (node (ref "U8") (pin "3") (pinfunction "PB2_(INT2/AIN0)_3") (pintype "bidirectional"))
    )
    (net (code "62") (name "/PB3") (class "Default")
      (node (ref "P1") (pin "7") (pinfunction "7_7") (pintype "passive"))
      (node (ref "P1") (pin "8") (pinfunction "8_8") (pintype "passive"))
      (node (ref "U8") (pin "4") (pinfunction "PB3_(OC0/AIN1)_4") (pintype "bidirectional"))
    )
    (net (code "63") (name "/PB4") (class "Default")
      (node (ref "P1") (pin "10") (pinfunction "10_10") (pintype "passive"))
      (node (ref "P1") (pin "9") (pinfunction "9_9") (pintype "passive"))
      (node (ref "U8") (pin "5") (pinfunction "PB4_(~{SS})_5") (pintype "bidirectional"))
    )
    (net (code "64") (name "/PB5") (class "Default")
      (node (ref "P1") (pin "11") (pinfunction "11_11") (pintype "passive"))
      (node (ref "P1") (pin "12") (pinfunction "12_12") (pintype "passive"))
      (node (ref "U8") (pin "6") (pinfunction "PB5_(MOSI)_6") (pintype "bidirectional"))
    )
    (net (code "65") (name "/PB6") (class "Default")
      (node (ref "P1") (pin "13") (pinfunction "13_13") (pintype "passive"))
      (node (ref "P1") (pin "14") (pinfunction "14_14") (pintype "passive"))
      (node (ref "U8") (pin "7") (pinfunction "PB6_(MISO)_7") (pintype "bidirectional"))
    )
    (net (code "66") (name "/PB7") (class "Default")
      (node (ref "P1") (pin "15") (pinfunction "15_15") (pintype "passive"))
      (node (ref "P1") (pin "16") (pinfunction "16_16") (pintype "passive"))
      (node (ref "U8") (pin "8") (pinfunction "PB7_(SCK)_8") (pintype "bidirectional"))
    )
    (net (code "67") (name "/PC0") (class "Default")
      (node (ref "P5") (pin "1") (pinfunction "1_1") (pintype "passive"))
      (node (ref "P5") (pin "2") (pinfunction "2_2") (pintype "passive"))
      (node (ref "U8") (pin "22") (pinfunction "PC0_(SCL)_22") (pintype "bidirectional"))
    )
    (net (code "68") (name "/PC1") (class "Default")
      (node (ref "P5") (pin "3") (pinfunction "3_3") (pintype "passive"))
      (node (ref "P5") (pin "4") (pinfunction "4_4") (pintype "passive"))
      (node (ref "U8") (pin "23") (pinfunction "PC1_(SDA)_23") (pintype "bidirectional"))
    )
    (net (code "69") (name "/PC6") (class "Default")
      (node (ref "P5") (pin "13") (pinfunction "13_13") (pintype "passive"))
      (node (ref "P5") (pin "14") (pinfunction "14_14") (pintype "passive"))
      (node (ref "U8") (pin "28") (pinfunction "PC6_(TOSC1)_28") (pintype "bidirectional"))
    )
    (net (code "70") (name "/PC7") (class "Default")
      (node (ref "P5") (pin "15") (pinfunction "15_15") (pintype "passive"))
      (node (ref "P5") (pin "16") (pinfunction "16_16") (pintype "passive"))
      (node (ref "U8") (pin "29") (pinfunction "PC7_(TOSC2)_29") (pintype "bidirectional"))
    )
    (net (code "71") (name "/PD0") (class "Default")
      (node (ref "P4") (pin "1") (pinfunction "1_1") (pintype "passive"))
      (node (ref "P4") (pin "2") (pinfunction "2_2") (pintype "passive"))
      (node (ref "U8") (pin "14") (pinfunction "PD0_(RXD)_14") (pintype "bidirectional"))
    )
    (net (code "72") (name "/PD1") (class "Default")
      (node (ref "P4") (pin "3") (pinfunction "3_3") (pintype "passive"))
      (node (ref "P4") (pin "4") (pinfunction "4_4") (pintype "passive"))
      (node (ref "U8") (pin "15") (pinfunction "PD1_(TXD)_15") (pintype "bidirectional"))
    )
    (net (code "73") (name "/PD2") (class "Default")
      (node (ref "P4") (pin "5") (pinfunction "5_5") (pintype "passive"))
      (node (ref "P4") (pin "6") (pinfunction "6_6") (pintype "passive"))
      (node (ref "U8") (pin "16") (pinfunction "PD2_(INT0)_16") (pintype "bidirectional"))
    )
    (net (code "74") (name "/PD3") (class "Default")
      (node (ref "P4") (pin "7") (pinfunction "7_7") (pintype "passive"))
      (node (ref "P4") (pin "8") (pinfunction "8_8") (pintype "passive"))
      (node (ref "U8") (pin "17") (pinfunction "PD3_(INT1)_17") (pintype "bidirectional"))
    )
    (net (code "75") (name "/PD4") (class "Default")
      (node (ref "P4") (pin "10") (pinfunction "10_10") (pintype "passive"))
      (node (ref "P4") (pin "9") (pinfunction "9_9") (pintype "passive"))
      (node (ref "U8") (pin "18") (pinfunction "PD4_(OC1B)_18") (pintype "bidirectional"))
    )
    (net (code "76") (name "/PD5") (class "Default")
      (node (ref "P4") (pin "11") (pinfunction "11_11") (pintype "passive"))
      (node (ref "P4") (pin "12") (pinfunction "12_12") (pintype "passive"))
      (node (ref "U8") (pin "19") (pinfunction "PD5_(OC1A)_19") (pintype "bidirectional"))
    )
    (net (code "77") (name "/PD6") (class "Default")
      (node (ref "P4") (pin "13") (pinfunction "13_13") (pintype "passive"))
      (node (ref "P4") (pin "14") (pinfunction "14_14") (pintype "passive"))
      (node (ref "U8") (pin "20") (pinfunction "PD6_(ICP1)_20") (pintype "bidirectional"))
    )
    (net (code "78") (name "/PD7") (class "Default")
      (node (ref "P4") (pin "15") (pinfunction "15_15") (pintype "passive"))
      (node (ref "P4") (pin "16") (pinfunction "16_16") (pintype "passive"))
      (node (ref "U8") (pin "21") (pinfunction "PD7_(OC2)_21") (pintype "bidirectional"))
    )
    (net (code "79") (name "/RAM nCE") (class "Default")
      (node (ref "R16") (pin "1") (pinfunction "1_1") (pintype "passive"))
      (node (ref "U2") (pin "20") (pinfunction "I/O_20") (pintype "passive"))
      (node (ref "U3") (pin "20") (pinfunction "~{CE}_20") (pintype "passive"))
    )
    (net (code "80") (name "/RAM nOE") (class "Default")
      (node (ref "U2") (pin "21") (pinfunction "I/O_21") (pintype "passive"))
      (node (ref "U3") (pin "22") (pinfunction "~{OE}_22") (pintype "passive"))
    )
    (net (code "81") (name "/RAM nWE") (class "Default")
      (node (ref "U2") (pin "19") (pinfunction "I/O_19") (pintype "passive"))
      (node (ref "U3") (pin "27") (pinfunction "~{WE}_27") (pintype "passive"))
    )
    (net (code "82") (name "/TCK_UUT") (class "Default")
      (node (ref "P5") (pin "5") (pinfunction "5_5") (pintype "passive"))
      (node (ref "P5") (pin "6") (pinfunction "6_6") (pintype "passive"))
      (node (ref "R3") (pin "2") (pinfunction "2_2") (pintype "passive"))
      (node (ref "U1") (pin "33") (pinfunction "TCK_33") (pintype "passive"))
      (node (ref "U2") (pin "11") (pinfunction "TCK_11") (pintype "passive"))
      (node (ref "U8") (pin "24") (pinfunction "PC2_(TCK)_24") (pintype "bidirectional"))
      (node (ref "XH1") (pin "1") (pinfunction "1_1") (pintype "passive"))
    )
    (net (code "83") (name "/TDI_UUT") (class "Default")
      (node (ref "P5") (pin "11") (pinfunction "11_11") (pintype "passive"))
      (node (ref "P5") (pin "12") (pinfunction "12_12") (pintype "passive"))
      (node (ref "R19") (pin "2") (pinfunction "2_2") (pintype "passive"))
      (node (ref "U1") (pin "34") (pinfunction "TDI_34") (pintype "passive"))
      (node (ref "U8") (pin "27") (pinfunction "PC5_(TDI)_27") (pintype "bidirectional"))
      (node (ref "XH1") (pin "7") (pinfunction "7_7") (pintype "passive"))
    )
    (net (code "84") (name "/TDO_U1") (class "Default")
      (node (ref "U1") (pin "31") (pinfunction "TDO_31") (pintype "passive"))
      (node (ref "U2") (pin "9") (pinfunction "TDI_9") (pintype "passive"))
    )
    (net (code "85") (name "/TDO_UUT") (class "Default")
      (node (ref "P5") (pin "10") (pinfunction "10_10") (pintype "passive"))
      (node (ref "P5") (pin "9") (pinfunction "9_9") (pintype "passive"))
      (node (ref "U2") (pin "24") (pinfunction "TDO_24") (pintype "passive"))
      (node (ref "U8") (pin "26") (pinfunction "PC4_(TDO)_26") (pintype "bidirectional"))
      (node (ref "XH1") (pin "5") (pinfunction "5_5") (pintype "passive"))
    )
    (net (code "86") (name "/TMS_UUT") (class "Default")
      (node (ref "P5") (pin "7") (pinfunction "7_7") (pintype "passive"))
      (node (ref "P5") (pin "8") (pinfunction "8_8") (pintype "passive"))
      (node (ref "R4") (pin "2") (pinfunction "2_2") (pintype "passive"))
      (node (ref "U1") (pin "32") (pinfunction "TMS_32") (pintype "passive"))
      (node (ref "U2") (pin "10") (pinfunction "TMS_10") (pintype "passive"))
      (node (ref "U8") (pin "25") (pinfunction "PC3_(TMS)_25") (pintype "bidirectional"))
      (node (ref "XH1") (pin "3") (pinfunction "3_3") (pintype "passive"))
    )
    (net (code "87") (name "/nOEAB") (class "Default")
      (node (ref "R1") (pin "1") (pinfunction "1_1") (pintype "passive"))
      (node (ref "U1") (pin "3") (pinfunction "~{1OEAB}_3") (pintype "passive"))
      (node (ref "U2") (pin "37") (pinfunction "I/O_37") (pintype "passive"))
    )
    (net (code "88") (name "/nOEBA") (class "Default")
      (node (ref "R2") (pin "1") (pinfunction "1_1") (pintype "passive"))
      (node (ref "U1") (pin "62") (pinfunction "~{1OEBA}_62") (pintype "passive"))
      (node (ref "U2") (pin "38") (pinfunction "I/O_38") (pintype "passive"))
    )
    (net (code "89") (name "3.3V") (class "Default")
      (node (ref "C10") (pin "1") (pinfunction "1_1") (pintype "passive"))
      (node (ref "C11") (pin "1") (pinfunction "1_1") (pintype "passive"))
      (node (ref "C14") (pin "1") (pinfunction "1_1") (pintype "passive"))
      (node (ref "C15") (pin "1") (pinfunction "1_1") (pintype "passive"))
      (node (ref "C16") (pin "1") (pinfunction "1_1") (pintype "passive"))
      (node (ref "C17") (pin "1") (pinfunction "1_1") (pintype "passive"))
      (node (ref "C2") (pin "1") (pinfunction "1_1") (pintype "passive"))
      (node (ref "C3") (pin "1") (pinfunction "1_1") (pintype "passive"))
      (node (ref "C4") (pin "1") (pinfunction "1_1") (pintype "passive"))
      (node (ref "C5") (pin "1") (pinfunction "1_1") (pintype "passive"))
      (node (ref "C6") (pin "1") (pinfunction "1_1") (pintype "passive"))
      (node (ref "C7") (pin "1") (pinfunction "1_1") (pintype "passive"))
      (node (ref "C8") (pin "1") (pinfunction "1_1") (pintype "passive"))
      (node (ref "C9") (pin "1") (pinfunction "1_1") (pintype "passive"))
      (node (ref "R1") (pin "2") (pinfunction "2_2") (pintype "passive"))
      (node (ref "R10") (pin "1") (pinfunction "1_1") (pintype "passive"))
      (node (ref "R14") (pin "1") (pinfunction "1_1") (pintype "passive"))
      (node (ref "R15") (pin "2") (pinfunction "2_2") (pintype "passive"))
      (node (ref "R16") (pin "2") (pinfunction "2_2") (pintype "passive"))
      (node (ref "R2") (pin "2") (pinfunction "2_2") (pintype "passive"))
      (node (ref "R20") (pin "2") (pinfunction "2_2") (pintype "passive"))
      (node (ref "R21") (pin "2") (pinfunction "2_2") (pintype "passive"))
      (node (ref "R6") (pin "1") (pinfunction "1_1") (pintype "passive"))
      (node (ref "R8") (pin "1") (pinfunction "1_1") (pintype "passive"))
      (node (ref "R9") (pin "2") (pinfunction "2_2") (pintype "passive"))
      (node (ref "SW1") (pin "3") (pinfunction "3_3") (pintype "passive"))
      (node (ref "SW1") (pin "4") (pinfunction "4_4") (pintype "passive"))
      (node (ref "U1") (pin "10") (pinfunction "VCC_10") (pintype "passive"))
      (node (ref "U1") (pin "23") (pinfunction "VCC_23") (pintype "passive"))
      (node (ref "U1") (pin "42") (pinfunction "VCC_42") (pintype "passive"))
      (node (ref "U1") (pin "55") (pinfunction "VCC_55") (pintype "passive"))
      (node (ref "U2") (pin "15") (pinfunction "VCCINT_15") (pintype "passive"))
      (node (ref "U2") (pin "26") (pinfunction "VCCIO_26") (pintype "passive"))
      (node (ref "U2") (pin "35") (pinfunction "VCCINT_35") (pintype "passive"))
      (node (ref "U3") (pin "28") (pinfunction "VCC_28") (pintype "passive"))
      (node (ref "U4") (pin "8") (pinfunction "VCC_8") (pintype "passive"))
      (node (ref "U5") (pin "12") (pinfunction "4A_12") (pintype "passive"))
      (node (ref "U5") (pin "14") (pinfunction "VCC_14") (pintype "passive"))
      (node (ref "U5") (pin "4") (pinfunction "2A_4") (pintype "passive"))
      (node (ref "U6") (pin "3") (pinfunction "OUT_3") (pintype "passive"))
      (node (ref "U7") (pin "4") (pinfunction "~{RESET}_4") (pintype "passive"))
      (node (ref "U7") (pin "8") (pinfunction "VCC_8") (pintype "passive"))
    )
    (net (code "90") (name "5V") (class "Default")
      (node (ref "C1") (pin "1") (pinfunction "1_1") (pintype "passive"))
      (node (ref "C21") (pin "1") (pinfunction "1_1") (pintype "passive"))
      (node (ref "C22") (pin "2") (pinfunction "2_2") (pintype "passive"))
      (node (ref "R32") (pin "1") (pinfunction "1_1") (pintype "passive"))
      (node (ref "U6") (pin "1") (pinfunction "IN_1") (pintype "passive"))
      (node (ref "U8") (pin "10") (pinfunction "VCC_10") (pintype "input"))
      (node (ref "U8") (pin "30") (pinfunction "AVCC_30") (pintype "input"))
      (node (ref "XH1") (pin "10") (pinfunction "10_10") (pintype "passive"))
    )
    (net (code "91") (name "GND") (class "Default")
      (node (ref "C1") (pin "2") (pinfunction "2_2") (pintype "passive"))
      (node (ref "C10") (pin "2") (pinfunction "2_2") (pintype "passive"))
      (node (ref "C11") (pin "2") (pinfunction "2_2") (pintype "passive"))
      (node (ref "C12") (pin "2") (pinfunction "2_2") (pintype "passive"))
      (node (ref "C13") (pin "2") (pinfunction "2_2") (pintype "passive"))
      (node (ref "C14") (pin "2") (pinfunction "2_2") (pintype "passive"))
      (node (ref "C15") (pin "2") (pinfunction "2_2") (pintype "passive"))
      (node (ref "C16") (pin "2") (pinfunction "2_2") (pintype "passive"))
      (node (ref "C17") (pin "2") (pinfunction "2_2") (pintype "passive"))
      (node (ref "C18") (pin "2") (pinfunction "2_2") (pintype "passive"))
      (node (ref "C19") (pin "2") (pinfunction "2_2") (pintype "passive"))
      (node (ref "C2") (pin "2") (pinfunction "2_2") (pintype "passive"))
      (node (ref "C20") (pin "2") (pinfunction "2_2") (pintype "passive"))
      (node (ref "C21") (pin "2") (pinfunction "2_2") (pintype "passive"))
      (node (ref "C22") (pin "1") (pinfunction "1_1") (pintype "passive"))
      (node (ref "C3") (pin "2") (pinfunction "2_2") (pintype "passive"))
      (node (ref "C4") (pin "2") (pinfunction "2_2") (pintype "passive"))
      (node (ref "C5") (pin "2") (pinfunction "2_2") (pintype "passive"))
      (node (ref "C6") (pin "2") (pinfunction "2_2") (pintype "passive"))
      (node (ref "C7") (pin "2") (pinfunction "2_2") (pintype "passive"))
      (node (ref "C8") (pin "2") (pinfunction "2_2") (pintype "passive"))
      (node (ref "C9") (pin "2") (pinfunction "2_2") (pintype "passive"))
      (node (ref "D1") (pin "1") (pinfunction "K_1") (pintype "output"))
      (node (ref "D10") (pin "1") (pinfunction "K_1") (pintype "output"))
      (node (ref "D2") (pin "1") (pinfunction "K_1") (pintype "output"))
      (node (ref "D3") (pin "1") (pinfunction "K_1") (pintype "output"))
      (node (ref "D4") (pin "1") (pinfunction "K_1") (pintype "output"))
      (node (ref "D5") (pin "1") (pinfunction "K_1") (pintype "output"))
      (node (ref "D6") (pin "1") (pinfunction "K_1") (pintype "output"))
      (node (ref "D7") (pin "1") (pinfunction "K_1") (pintype "output"))
      (node (ref "D8") (pin "1") (pinfunction "K_1") (pintype "output"))
      (node (ref "D9") (pin "1") (pinfunction "K_1") (pintype "output"))
      (node (ref "R11") (pin "1") (pinfunction "1_1") (pintype "passive"))
      (node (ref "R13") (pin "1") (pinfunction "1_1") (pintype "passive"))
      (node (ref "R18") (pin "1") (pinfunction "1_1") (pintype "passive"))
      (node (ref "R19") (pin "1") (pinfunction "1_1") (pintype "passive"))
      (node (ref "R3") (pin "1") (pinfunction "1_1") (pintype "passive"))
      (node (ref "R4") (pin "1") (pinfunction "1_1") (pintype "passive"))
      (node (ref "SW2") (pin "1") (pinfunction "1_1") (pintype "passive"))
      (node (ref "SW2") (pin "2") (pinfunction "2_2") (pintype "passive"))
      (node (ref "U1") (pin "14") (pinfunction "GND_14") (pintype "passive"))
      (node (ref "U1") (pin "19") (pinfunction "GND_19") (pintype "passive"))
      (node (ref "U1") (pin "27") (pinfunction "GND_27") (pintype "passive"))
      (node (ref "U1") (pin "38") (pinfunction "GND_38") (pintype "passive"))
      (node (ref "U1") (pin "46") (pinfunction "GND_46") (pintype "passive"))
      (node (ref "U1") (pin "51") (pinfunction "GND_51") (pintype "passive"))
      (node (ref "U1") (pin "59") (pinfunction "GND_59") (pintype "passive"))
      (node (ref "U1") (pin "6") (pinfunction "GND_6") (pintype "passive"))
      (node (ref "U2") (pin "17") (pinfunction "GND_17") (pintype "passive"))
      (node (ref "U2") (pin "25") (pinfunction "GND_25") (pintype "passive"))
      (node (ref "U2") (pin "4") (pinfunction "GND_4") (pintype "passive"))
      (node (ref "U3") (pin "1") (pinfunction "A14_1") (pintype "passive"))
      (node (ref "U3") (pin "14") (pinfunction "GND_14") (pintype "passive"))
      (node (ref "U3") (pin "2") (pinfunction "A12_2") (pintype "passive"))
      (node (ref "U3") (pin "21") (pinfunction "A10_21") (pintype "passive"))
      (node (ref "U3") (pin "23") (pinfunction "A11_23") (pintype "passive"))
      (node (ref "U3") (pin "26") (pinfunction "A13_26") (pintype "passive"))
      (node (ref "U4") (pin "1") (pinfunction "E0_1") (pintype "passive"))
      (node (ref "U4") (pin "2") (pinfunction "E1_2") (pintype "passive"))
      (node (ref "U4") (pin "3") (pinfunction "E2_3") (pintype "passive"))
      (node (ref "U4") (pin "4") (pinfunction "GND_4") (pintype "passive"))
      (node (ref "U4") (pin "7") (pinfunction "~{WC}_7") (pintype "passive"))
      (node (ref "U5") (pin "7") (pinfunction "GND_7") (pintype "passive"))
      (node (ref "U6") (pin "2") (pinfunction "GND_2") (pintype "passive"))
      (node (ref "U6") (pin "4") (pinfunction "GND_4") (pintype "passive"))
      (node (ref "U7") (pin "1") (pinfunction "GND_1") (pintype "passive"))
      (node (ref "U8") (pin "11") (pinfunction "GND_11") (pintype "power_in"))
      (node (ref "U8") (pin "31") (pinfunction "GND_31") (pintype "power_in"))
      (node (ref "XH1") (pin "2") (pinfunction "2_2") (pintype "passive"))
      (node (ref "XH1") (pin "4") (pinfunction "4_4") (pintype "passive"))
      (node (ref "XH1") (pin "6") (pinfunction "6_6") (pintype "passive"))
      (node (ref "XH1") (pin "8") (pinfunction "8_8") (pintype "passive"))
    )
    (net (code "92") (name "Net-(D1-A)") (class "Default")
      (node (ref "D1") (pin "2") (pinfunction "A_2") (pintype "input"))
      (node (ref "R22") (pin "1") (pinfunction "1_1") (pintype "passive"))
    )
    (net (code "93") (name "Net-(D2-A)") (class "Default")
      (node (ref "D2") (pin "2") (pinfunction "A_2") (pintype "input"))
      (node (ref "R23") (pin "1") (pinfunction "1_1") (pintype "passive"))
    )
    (net (code "94") (name "Net-(D3-A)") (class "Default")
      (node (ref "D3") (pin "2") (pinfunction "A_2") (pintype "input"))
      (node (ref "R24") (pin "1") (pinfunction "1_1") (pintype "passive"))
    )
    (net (code "95") (name "Net-(D4-A)") (class "Default")
      (node (ref "D4") (pin "2") (pinfunction "A_2") (pintype "input"))
      (node (ref "R25") (pin "1") (pinfunction "1_1") (pintype "passive"))
    )
    (net (code "96") (name "Net-(D5-A)") (class "Default")
      (node (ref "D5") (pin "2") (pinfunction "A_2") (pintype "input"))
      (node (ref "R26") (pin "1") (pinfunction "1_1") (pintype "passive"))
    )
    (net (code "97") (name "Net-(D6-A)") (class "Default")
      (node (ref "D6") (pin "2") (pinfunction "A_2") (pintype "input"))
      (node (ref "R27") (pin "1") (pinfunction "1_1") (pintype "passive"))
    )
    (net (code "98") (name "Net-(D7-A)") (class "Default")
      (node (ref "D7") (pin "2") (pinfunction "A_2") (pintype "input"))
      (node (ref "R28") (pin "1") (pinfunction "1_1") (pintype "passive"))
    )
    (net (code "99") (name "Net-(D8-A)") (class "Default")
      (node (ref "D8") (pin "2") (pinfunction "A_2") (pintype "input"))
      (node (ref "R29") (pin "1") (pinfunction "1_1") (pintype "passive"))
    )
    (net (code "100") (name "Net-(D9-A)") (class "Default")
      (node (ref "D9") (pin "2") (pinfunction "A_2") (pintype "input"))
      (node (ref "R30") (pin "1") (pinfunction "1_1") (pintype "passive"))
    )
    (net (code "101") (name "Net-(D10-A)") (class "Default")
      (node (ref "D10") (pin "2") (pinfunction "A_2") (pintype "input"))
      (node (ref "R31") (pin "1") (pinfunction "1_1") (pintype "passive"))
    )
    (net (code "102") (name "Net-(R13-Pad2)") (class "Default")
      (node (ref "R13") (pin "2") (pinfunction "2_2") (pintype "passive"))
      (node (ref "SW1") (pin "1") (pinfunction "1_1") (pintype "passive"))
      (node (ref "SW1") (pin "2") (pinfunction "2_2") (pintype "passive"))
      (node (ref "U2") (pin "33") (pinfunction "I/O_33") (pintype "passive"))
    )
    (net (code "103") (name "Net-(S1-A2)") (class "Default")
      (node (ref "R17") (pin "2") (pinfunction "2_2") (pintype "passive"))
      (node (ref "S1") (pin "8") (pinfunction "A2_8") (pintype "passive"))
    )
    (net (code "104") (name "Net-(S1-B2)") (class "Default")
      (node (ref "R12") (pin "2") (pinfunction "2_2") (pintype "passive"))
      (node (ref "S1") (pin "7") (pinfunction "B2_7") (pintype "passive"))
    )
    (net (code "105") (name "Net-(S1-C2)") (class "Default")
      (node (ref "R11") (pin "2") (pinfunction "2_2") (pintype "passive"))
      (node (ref "S1") (pin "6") (pinfunction "C2_6") (pintype "passive"))
    )
    (net (code "106") (name "Net-(S1-D2)") (class "Default")
      (node (ref "R10") (pin "2") (pinfunction "2_2") (pintype "passive"))
      (node (ref "S1") (pin "5") (pinfunction "D2_5") (pintype "passive"))
    )
    (net (code "107") (name "Net-(U1-1LEAB)") (class "Default")
      (node (ref "R8") (pin "2") (pinfunction "2_2") (pintype "passive"))
      (node (ref "U1") (pin "2") (pinfunction "1LEAB_2") (pintype "passive"))
    )
    (net (code "108") (name "Net-(U1-1LEBA)") (class "Default")
      (node (ref "R9") (pin "1") (pinfunction "1_1") (pintype "passive"))
      (node (ref "U1") (pin "63") (pinfunction "1LEBA_63") (pintype "passive"))
    )
    (net (code "109") (name "Net-(U1-2LEAB)") (class "Default")
      (node (ref "R14") (pin "2") (pinfunction "2_2") (pintype "passive"))
      (node (ref "U1") (pin "28") (pinfunction "~{2OEAB}_28") (pintype "passive"))
      (node (ref "U1") (pin "29") (pinfunction "2LEAB_29") (pintype "passive"))
    )
    (net (code "110") (name "Net-(U1-2LEBA)") (class "Default")
      (node (ref "R15") (pin "1") (pinfunction "1_1") (pintype "passive"))
      (node (ref "U1") (pin "36") (pinfunction "2LEBA_36") (pintype "passive"))
    )
    (net (code "111") (name "Net-(U1-~{2OEBA})") (class "Default")
      (node (ref "R18") (pin "2") (pinfunction "2_2") (pintype "passive"))
      (node (ref "U1") (pin "37") (pinfunction "~{2OEBA}_37") (pintype "passive"))
    )
    (net (code "112") (name "Net-(U2-I{slash}O,_GCK1)") (class "Default")
      (node (ref "R7") (pin "1") (pinfunction "1_1") (pintype "passive"))
      (node (ref "U2") (pin "43") (pinfunction "I/O,_GCK1_43") (pintype "passive"))
    )
    (net (code "113") (name "Net-(U7-CTRLV)") (class "Default")
      (node (ref "C13") (pin "1") (pinfunction "1_1") (pintype "passive"))
      (node (ref "U7") (pin "5") (pinfunction "CTRLV_5") (pintype "passive"))
    )
    (net (code "114") (name "Net-(U7-DISCHARGE)") (class "Default")
      (node (ref "R5") (pin "1") (pinfunction "1_1") (pintype "passive"))
      (node (ref "R6") (pin "2") (pinfunction "2_2") (pintype "passive"))
      (node (ref "U7") (pin "7") (pinfunction "DISCHARGE_7") (pintype "passive"))
    )
    (net (code "115") (name "Net-(U7-OUTPUT)") (class "Default")
      (node (ref "R7") (pin "2") (pinfunction "2_2") (pintype "passive"))
      (node (ref "U7") (pin "3") (pinfunction "OUTPUT_3") (pintype "passive"))
    )
    (net (code "116") (name "Net-(U7-THRESH)") (class "Default")
      (node (ref "C12") (pin "1") (pinfunction "1_1") (pintype "passive"))
      (node (ref "R5") (pin "2") (pinfunction "2_2") (pintype "passive"))
      (node (ref "U7") (pin "2") (pinfunction "~{TRIGGER}_2") (pintype "passive"))
      (node (ref "U7") (pin "6") (pinfunction "THRESH_6") (pintype "passive"))
    )
    (net (code "117") (name "Net-(U8-AREF)") (class "Default")
      (node (ref "C20") (pin "1") (pinfunction "1_1") (pintype "passive"))
      (node (ref "P3") (pin "1") (pinfunction "1_1") (pintype "passive"))
      (node (ref "P3") (pin "2") (pinfunction "2_2") (pintype "passive"))
      (node (ref "U8") (pin "32") (pinfunction "AREF_32") (pintype "input"))
    )
    (net (code "118") (name "Net-(U8-XTAL1)") (class "Default")
      (node (ref "C19") (pin "1") (pinfunction "1_1") (pintype "passive"))
      (node (ref "U8") (pin "13") (pinfunction "XTAL1_13") (pintype "input"))
      (node (ref "X1") (pin "2") (pintype "passive"))
    )
    (net (code "119") (name "Net-(U8-XTAL2)") (class "Default")
      (node (ref "C18") (pin "1") (pinfunction "1_1") (pintype "passive"))
      (node (ref "U8") (pin "12") (pinfunction "XTAL2_12") (pintype "input"))
      (node (ref "X1") (pin "1") (pintype "passive"))
    )
    (net (code "120") (name "Net-(U8-~{RESET})") (class "Default")
      (node (ref "R32") (pin "2") (pinfunction "2_2") (pintype "passive"))
      (node (ref "SW2") (pin "3") (pinfunction "3_3") (pintype "passive"))
      (node (ref "SW2") (pin "4") (pinfunction "4_4") (pintype "passive"))
      (node (ref "U8") (pin "9") (pinfunction "~{RESET}_9") (pintype "input"))
    )
    (net (code "121") (name "unconnected-(U1-1CLKAB-Pad1)") (class "Default")
      (node (ref "U1") (pin "1") (pinfunction "1CLKAB_1") (pintype "passive"))
    )
    (net (code "122") (name "unconnected-(U1-1CLKBA-Pad64)") (class "Default")
      (node (ref "U1") (pin "64") (pinfunction "1CLKBA_64") (pintype "passive"))
    )
    (net (code "123") (name "unconnected-(U1-2CLKAB-Pad30)") (class "Default")
      (node (ref "U1") (pin "30") (pinfunction "2CLKAB_30") (pintype "passive"))
    )
    (net (code "124") (name "unconnected-(U1-2CLKBA-Pad35)") (class "Default")
      (node (ref "U1") (pin "35") (pinfunction "2CLKBA_35") (pintype "passive"))
    )
    (net (code "125") (name "unconnected-(U2-I{slash}O-Pad36)") (class "Default")
      (node (ref "U2") (pin "36") (pinfunction "I/O_36") (pintype "passive"))
    )
    (net (code "126") (name "unconnected-(XH1-Pad9)") (class "Default")
      (node (ref "XH1") (pin "9") (pinfunction "9_9") (pintype "passive"))
    )
  )
)
